# panelPrimer.net
KiCad netlist of a schematic drawn in EAGLE
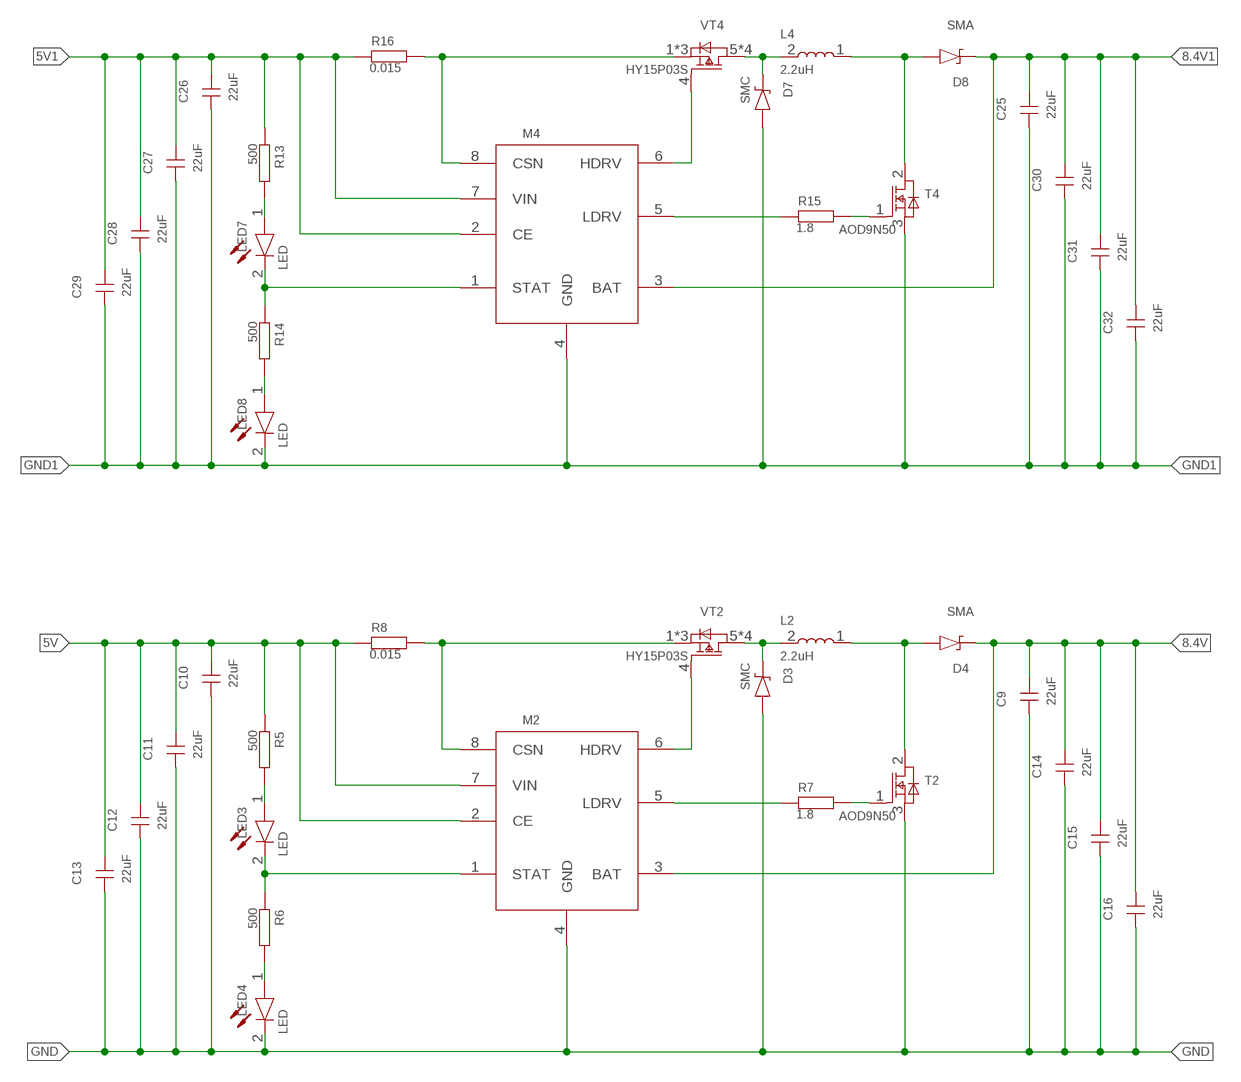
[diagram p0: schematic, sheet 1]

(export (version "E")
  (design (tool "Eeschema 10.0.6"))
  (components
    (comp (ref "C9")
      (value "22uF")
      (footprint "eagle-import:1206")
      (libsource (lib "eagle-import") (part "CAPACITOR"))
    )
    (comp (ref "C10")
      (value "22uF")
      (footprint "eagle-import:1206")
      (libsource (lib "eagle-import") (part "CAPACITOR"))
    )
    (comp (ref "C11")
      (value "22uF")
      (footprint "eagle-import:1206")
      (libsource (lib "eagle-import") (part "CAPACITOR"))
    )
    (comp (ref "C12")
      (value "22uF")
      (footprint "eagle-import:1206")
      (libsource (lib "eagle-import") (part "CAPACITOR"))
    )
    (comp (ref "C13")
      (value "22uF")
      (footprint "eagle-import:1206")
      (libsource (lib "eagle-import") (part "CAPACITOR"))
    )
    (comp (ref "C14")
      (value "22uF")
      (footprint "eagle-import:1206")
      (libsource (lib "eagle-import") (part "CAPACITOR"))
    )
    (comp (ref "C15")
      (value "22uF")
      (footprint "eagle-import:1206")
      (libsource (lib "eagle-import") (part "CAPACITOR"))
    )
    (comp (ref "C16")
      (value "22uF")
      (footprint "eagle-import:1206")
      (libsource (lib "eagle-import") (part "CAPACITOR"))
    )
    (comp (ref "C25")
      (value "22uF")
      (footprint "eagle-import:1206")
      (libsource (lib "eagle-import") (part "CAPACITOR"))
    )
    (comp (ref "C26")
      (value "22uF")
      (footprint "eagle-import:1206")
      (libsource (lib "eagle-import") (part "CAPACITOR"))
    )
    (comp (ref "C27")
      (value "22uF")
      (footprint "eagle-import:1206")
      (libsource (lib "eagle-import") (part "CAPACITOR"))
    )
    (comp (ref "C28")
      (value "22uF")
      (footprint "eagle-import:1206")
      (libsource (lib "eagle-import") (part "CAPACITOR"))
    )
    (comp (ref "C29")
      (value "22uF")
      (footprint "eagle-import:1206")
      (libsource (lib "eagle-import") (part "CAPACITOR"))
    )
    (comp (ref "C30")
      (value "22uF")
      (footprint "eagle-import:1206")
      (libsource (lib "eagle-import") (part "CAPACITOR"))
    )
    (comp (ref "C31")
      (value "22uF")
      (footprint "eagle-import:1206")
      (libsource (lib "eagle-import") (part "CAPACITOR"))
    )
    (comp (ref "C32")
      (value "22uF")
      (footprint "eagle-import:1206")
      (libsource (lib "eagle-import") (part "CAPACITOR"))
    )
    (comp (ref "D3")
      (value "SMC")
      (footprint "eagle-import:SMC")
      (libsource (lib "eagle-import") (part "DIODESSMC"))
    )
    (comp (ref "D4")
      (value "SMA")
      (footprint "eagle-import:SMA")
      (libsource (lib "eagle-import") (part "DIODESSMA"))
    )
    (comp (ref "D7")
      (value "SMC")
      (footprint "eagle-import:SMC")
      (libsource (lib "eagle-import") (part "DIODESSMC"))
    )
    (comp (ref "D8")
      (value "SMA")
      (footprint "eagle-import:SMA")
      (libsource (lib "eagle-import") (part "DIODESSMA"))
    )
    (comp (ref "L2")
      (value "2.2uH")
      (footprint "eagle-import:FXL0530")
      (libsource (lib "eagle-import") (part "INDUCTORFXL0530-2R2-M"))
    )
    (comp (ref "L4")
      (value "2.2uH")
      (footprint "eagle-import:FXL0530")
      (libsource (lib "eagle-import") (part "INDUCTORFXL0530-2R2-M"))
    )
    (comp (ref "LED3")
      (value "LED")
      (footprint "eagle-import:LED")
      (libsource (lib "eagle-import") (part "LED"))
    )
    (comp (ref "LED4")
      (value "LED")
      (footprint "eagle-import:LED")
      (libsource (lib "eagle-import") (part "LED"))
    )
    (comp (ref "LED7")
      (value "LED")
      (footprint "eagle-import:LED")
      (libsource (lib "eagle-import") (part "LED"))
    )
    (comp (ref "LED8")
      (value "LED")
      (footprint "eagle-import:LED")
      (libsource (lib "eagle-import") (part "LED"))
    )
    (comp (ref "M2")
      (value "CN3302SOP-8")
      (footprint "eagle-import:SOP-8")
      (libsource (lib "eagle-import") (part "CN3302SOP-8"))
    )
    (comp (ref "M4")
      (value "CN3302SOP-8")
      (footprint "eagle-import:SOP-8")
      (libsource (lib "eagle-import") (part "CN3302SOP-8"))
    )
    (comp (ref "R5")
      (value "500")
      (footprint "eagle-import:0603")
      (libsource (lib "eagle-import") (part "RESISTOR0603"))
    )
    (comp (ref "R6")
      (value "500")
      (footprint "eagle-import:0603")
      (libsource (lib "eagle-import") (part "RESISTOR0603"))
    )
    (comp (ref "R7")
      (value "1.8")
      (footprint "eagle-import:0603")
      (libsource (lib "eagle-import") (part "RESISTOR0603"))
    )
    (comp (ref "R8")
      (value "0.015")
      (footprint "eagle-import:2512")
      (libsource (lib "eagle-import") (part "RESISTOR2512"))
    )
    (comp (ref "R13")
      (value "500")
      (footprint "eagle-import:0603")
      (libsource (lib "eagle-import") (part "RESISTOR0603"))
    )
    (comp (ref "R14")
      (value "500")
      (footprint "eagle-import:0603")
      (libsource (lib "eagle-import") (part "RESISTOR0603"))
    )
    (comp (ref "R15")
      (value "1.8")
      (footprint "eagle-import:0603")
      (libsource (lib "eagle-import") (part "RESISTOR0603"))
    )
    (comp (ref "R16")
      (value "0.015")
      (footprint "eagle-import:2512")
      (libsource (lib "eagle-import") (part "RESISTOR2512"))
    )
    (comp (ref "T2")
      (value "AOD9N50")
      (footprint "eagle-import:DRACK")
      (libsource (lib "eagle-import") (part "AOD9N50"))
    )
    (comp (ref "T4")
      (value "AOD9N50")
      (footprint "eagle-import:DRACK")
      (libsource (lib "eagle-import") (part "AOD9N50"))
    )
    (comp (ref "VT2")
      (value "HY15P03S")
      (footprint "eagle-import:SOP-8")
      (libsource (lib "eagle-import") (part "HY15P03S"))
    )
    (comp (ref "VT4")
      (value "HY15P03S")
      (footprint "eagle-import:SOP-8")
      (libsource (lib "eagle-import") (part "HY15P03S"))
    )
  )
  (nets
    (net (code "1") (name "5V") (class "Default")
      (node (ref "C10") (pin "2") (pinfunction "P$2_2") (pintype "bidirectional"))
      (node (ref "C11") (pin "2") (pinfunction "P$2_2") (pintype "bidirectional"))
      (node (ref "C12") (pin "2") (pinfunction "P$2_2") (pintype "bidirectional"))
      (node (ref "C13") (pin "2") (pinfunction "P$2_2") (pintype "bidirectional"))
      (node (ref "M2") (pin "2") (pinfunction "CE_2") (pintype "input"))
      (node (ref "M2") (pin "7") (pinfunction "VIN_7") (pintype "output"))
      (node (ref "R5") (pin "1") (pinfunction "P$1_1") (pintype "bidirectional"))
      (node (ref "R8") (pin "1") (pinfunction "P$1_1") (pintype "bidirectional"))
    )
    (net (code "2") (name "5V1") (class "Default")
      (node (ref "C26") (pin "2") (pinfunction "P$2_2") (pintype "bidirectional"))
      (node (ref "C27") (pin "2") (pinfunction "P$2_2") (pintype "bidirectional"))
      (node (ref "C28") (pin "2") (pinfunction "P$2_2") (pintype "bidirectional"))
      (node (ref "C29") (pin "2") (pinfunction "P$2_2") (pintype "bidirectional"))
      (node (ref "M4") (pin "2") (pinfunction "CE_2") (pintype "input"))
      (node (ref "M4") (pin "7") (pinfunction "VIN_7") (pintype "output"))
      (node (ref "R13") (pin "1") (pinfunction "P$1_1") (pintype "bidirectional"))
      (node (ref "R16") (pin "1") (pinfunction "P$1_1") (pintype "bidirectional"))
    )
    (net (code "3") (name "8.4V") (class "Default")
      (node (ref "C14") (pin "2") (pinfunction "P$2_2") (pintype "bidirectional"))
      (node (ref "C15") (pin "2") (pinfunction "P$2_2") (pintype "bidirectional"))
      (node (ref "C16") (pin "2") (pinfunction "P$2_2") (pintype "bidirectional"))
      (node (ref "C9") (pin "2") (pinfunction "P$2_2") (pintype "bidirectional"))
      (node (ref "D4") (pin "2") (pinfunction "C_2") (pintype "output"))
      (node (ref "M2") (pin "3") (pinfunction "BAT_3") (pintype "input"))
    )
    (net (code "4") (name "8.4V1") (class "Default")
      (node (ref "C25") (pin "2") (pinfunction "P$2_2") (pintype "bidirectional"))
      (node (ref "C30") (pin "2") (pinfunction "P$2_2") (pintype "bidirectional"))
      (node (ref "C31") (pin "2") (pinfunction "P$2_2") (pintype "bidirectional"))
      (node (ref "C32") (pin "2") (pinfunction "P$2_2") (pintype "bidirectional"))
      (node (ref "D8") (pin "2") (pinfunction "C_2") (pintype "output"))
      (node (ref "M4") (pin "3") (pinfunction "BAT_3") (pintype "input"))
    )
    (net (code "5") (name "GND") (class "Default")
      (node (ref "C10") (pin "1") (pinfunction "P$1_1") (pintype "bidirectional"))
      (node (ref "C11") (pin "1") (pinfunction "P$1_1") (pintype "bidirectional"))
      (node (ref "C12") (pin "1") (pinfunction "P$1_1") (pintype "bidirectional"))
      (node (ref "C13") (pin "1") (pinfunction "P$1_1") (pintype "bidirectional"))
      (node (ref "C14") (pin "1") (pinfunction "P$1_1") (pintype "bidirectional"))
      (node (ref "C15") (pin "1") (pinfunction "P$1_1") (pintype "bidirectional"))
      (node (ref "C16") (pin "1") (pinfunction "P$1_1") (pintype "bidirectional"))
      (node (ref "C9") (pin "1") (pinfunction "P$1_1") (pintype "bidirectional"))
      (node (ref "D3") (pin "1") (pinfunction "A_1") (pintype "input"))
      (node (ref "LED4") (pin "2") (pinfunction "CATHODE_2") (pintype "output"))
      (node (ref "M2") (pin "4") (pinfunction "GND_4") (pintype "power_in"))
      (node (ref "T2") (pin "3") (pinfunction "S_3") (pintype "output"))
    )
    (net (code "6") (name "GND1") (class "Default")
      (node (ref "C25") (pin "1") (pinfunction "P$1_1") (pintype "bidirectional"))
      (node (ref "C26") (pin "1") (pinfunction "P$1_1") (pintype "bidirectional"))
      (node (ref "C27") (pin "1") (pinfunction "P$1_1") (pintype "bidirectional"))
      (node (ref "C28") (pin "1") (pinfunction "P$1_1") (pintype "bidirectional"))
      (node (ref "C29") (pin "1") (pinfunction "P$1_1") (pintype "bidirectional"))
      (node (ref "C30") (pin "1") (pinfunction "P$1_1") (pintype "bidirectional"))
      (node (ref "C31") (pin "1") (pinfunction "P$1_1") (pintype "bidirectional"))
      (node (ref "C32") (pin "1") (pinfunction "P$1_1") (pintype "bidirectional"))
      (node (ref "D7") (pin "1") (pinfunction "A_1") (pintype "input"))
      (node (ref "LED8") (pin "2") (pinfunction "CATHODE_2") (pintype "output"))
      (node (ref "M4") (pin "4") (pinfunction "GND_4") (pintype "power_in"))
      (node (ref "T4") (pin "3") (pinfunction "S_3") (pintype "output"))
    )
    (net (code "7") (name "Net-(D3-C)") (class "Default")
      (node (ref "D3") (pin "2") (pinfunction "C_2") (pintype "output"))
      (node (ref "L2") (pin "2") (pinfunction "2_2") (pintype "bidirectional"))
      (node (ref "VT2") (pin "5") (pinfunction "D_5") (pintype "output"))
      (node (ref "VT2") (pin "6") (pinfunction "D_6") (pintype "output"))
      (node (ref "VT2") (pin "7") (pinfunction "D_7") (pintype "output"))
      (node (ref "VT2") (pin "8") (pinfunction "D_8") (pintype "output"))
    )
    (net (code "8") (name "Net-(D4-A)") (class "Default")
      (node (ref "D4") (pin "1") (pinfunction "A_1") (pintype "input"))
      (node (ref "L2") (pin "1") (pinfunction "1_1") (pintype "bidirectional"))
      (node (ref "T2") (pin "2") (pinfunction "D_2") (pintype "input"))
    )
    (net (code "9") (name "Net-(D7-C)") (class "Default")
      (node (ref "D7") (pin "2") (pinfunction "C_2") (pintype "output"))
      (node (ref "L4") (pin "2") (pinfunction "2_2") (pintype "bidirectional"))
      (node (ref "VT4") (pin "5") (pinfunction "D_5") (pintype "output"))
      (node (ref "VT4") (pin "6") (pinfunction "D_6") (pintype "output"))
      (node (ref "VT4") (pin "7") (pinfunction "D_7") (pintype "output"))
      (node (ref "VT4") (pin "8") (pinfunction "D_8") (pintype "output"))
    )
    (net (code "10") (name "Net-(D8-A)") (class "Default")
      (node (ref "D8") (pin "1") (pinfunction "A_1") (pintype "input"))
      (node (ref "L4") (pin "1") (pinfunction "1_1") (pintype "bidirectional"))
      (node (ref "T4") (pin "2") (pinfunction "D_2") (pintype "input"))
    )
    (net (code "11") (name "Net-(LED3-ANODE)") (class "Default")
      (node (ref "LED3") (pin "1") (pinfunction "ANODE_1") (pintype "input"))
      (node (ref "R5") (pin "2") (pinfunction "P$2_2") (pintype "bidirectional"))
    )
    (net (code "12") (name "Net-(LED3-CATHODE)") (class "Default")
      (node (ref "LED3") (pin "2") (pinfunction "CATHODE_2") (pintype "output"))
      (node (ref "M2") (pin "1") (pinfunction "STAT_1") (pintype "input"))
      (node (ref "R6") (pin "1") (pinfunction "P$1_1") (pintype "bidirectional"))
    )
    (net (code "13") (name "Net-(LED4-ANODE)") (class "Default")
      (node (ref "LED4") (pin "1") (pinfunction "ANODE_1") (pintype "input"))
      (node (ref "R6") (pin "2") (pinfunction "P$2_2") (pintype "bidirectional"))
    )
    (net (code "14") (name "Net-(LED7-ANODE)") (class "Default")
      (node (ref "LED7") (pin "1") (pinfunction "ANODE_1") (pintype "input"))
      (node (ref "R13") (pin "2") (pinfunction "P$2_2") (pintype "bidirectional"))
    )
    (net (code "15") (name "Net-(LED7-CATHODE)") (class "Default")
      (node (ref "LED7") (pin "2") (pinfunction "CATHODE_2") (pintype "output"))
      (node (ref "M4") (pin "1") (pinfunction "STAT_1") (pintype "input"))
      (node (ref "R14") (pin "1") (pinfunction "P$1_1") (pintype "bidirectional"))
    )
    (net (code "16") (name "Net-(LED8-ANODE)") (class "Default")
      (node (ref "LED8") (pin "1") (pinfunction "ANODE_1") (pintype "input"))
      (node (ref "R14") (pin "2") (pinfunction "P$2_2") (pintype "bidirectional"))
    )
    (net (code "17") (name "Net-(M2-CSN)") (class "Default")
      (node (ref "M2") (pin "8") (pinfunction "CSN_8") (pintype "output"))
      (node (ref "R8") (pin "2") (pinfunction "P$2_2") (pintype "bidirectional"))
      (node (ref "VT2") (pin "1") (pinfunction "S_1") (pintype "input"))
      (node (ref "VT2") (pin "2") (pinfunction "S_2") (pintype "input"))
      (node (ref "VT2") (pin "3") (pinfunction "S_3") (pintype "input"))
    )
    (net (code "18") (name "Net-(M2-HDRV)") (class "Default")
      (node (ref "M2") (pin "6") (pinfunction "HDRV_6") (pintype "output"))
      (node (ref "VT2") (pin "4") (pinfunction "G_4") (pintype "power_in"))
    )
    (net (code "19") (name "Net-(M2-LDRV)") (class "Default")
      (node (ref "M2") (pin "5") (pinfunction "LDRV_5") (pintype "output"))
      (node (ref "R7") (pin "1") (pinfunction "P$1_1") (pintype "bidirectional"))
    )
    (net (code "20") (name "Net-(M4-CSN)") (class "Default")
      (node (ref "M4") (pin "8") (pinfunction "CSN_8") (pintype "output"))
      (node (ref "R16") (pin "2") (pinfunction "P$2_2") (pintype "bidirectional"))
      (node (ref "VT4") (pin "1") (pinfunction "S_1") (pintype "input"))
      (node (ref "VT4") (pin "2") (pinfunction "S_2") (pintype "input"))
      (node (ref "VT4") (pin "3") (pinfunction "S_3") (pintype "input"))
    )
    (net (code "21") (name "Net-(M4-HDRV)") (class "Default")
      (node (ref "M4") (pin "6") (pinfunction "HDRV_6") (pintype "output"))
      (node (ref "VT4") (pin "4") (pinfunction "G_4") (pintype "power_in"))
    )
    (net (code "22") (name "Net-(M4-LDRV)") (class "Default")
      (node (ref "M4") (pin "5") (pinfunction "LDRV_5") (pintype "output"))
      (node (ref "R15") (pin "1") (pinfunction "P$1_1") (pintype "bidirectional"))
    )
    (net (code "23") (name "Net-(R7-P$2)") (class "Default")
      (node (ref "R7") (pin "2") (pinfunction "P$2_2") (pintype "bidirectional"))
      (node (ref "T2") (pin "1") (pinfunction "G_1") (pintype "power_in"))
    )
    (net (code "24") (name "Net-(R15-P$2)") (class "Default")
      (node (ref "R15") (pin "2") (pinfunction "P$2_2") (pintype "bidirectional"))
      (node (ref "T4") (pin "1") (pinfunction "G_1") (pintype "power_in"))
    )
  )
)
